# openTPM.net
KiCad netlist of a schematic drawn in EAGLE
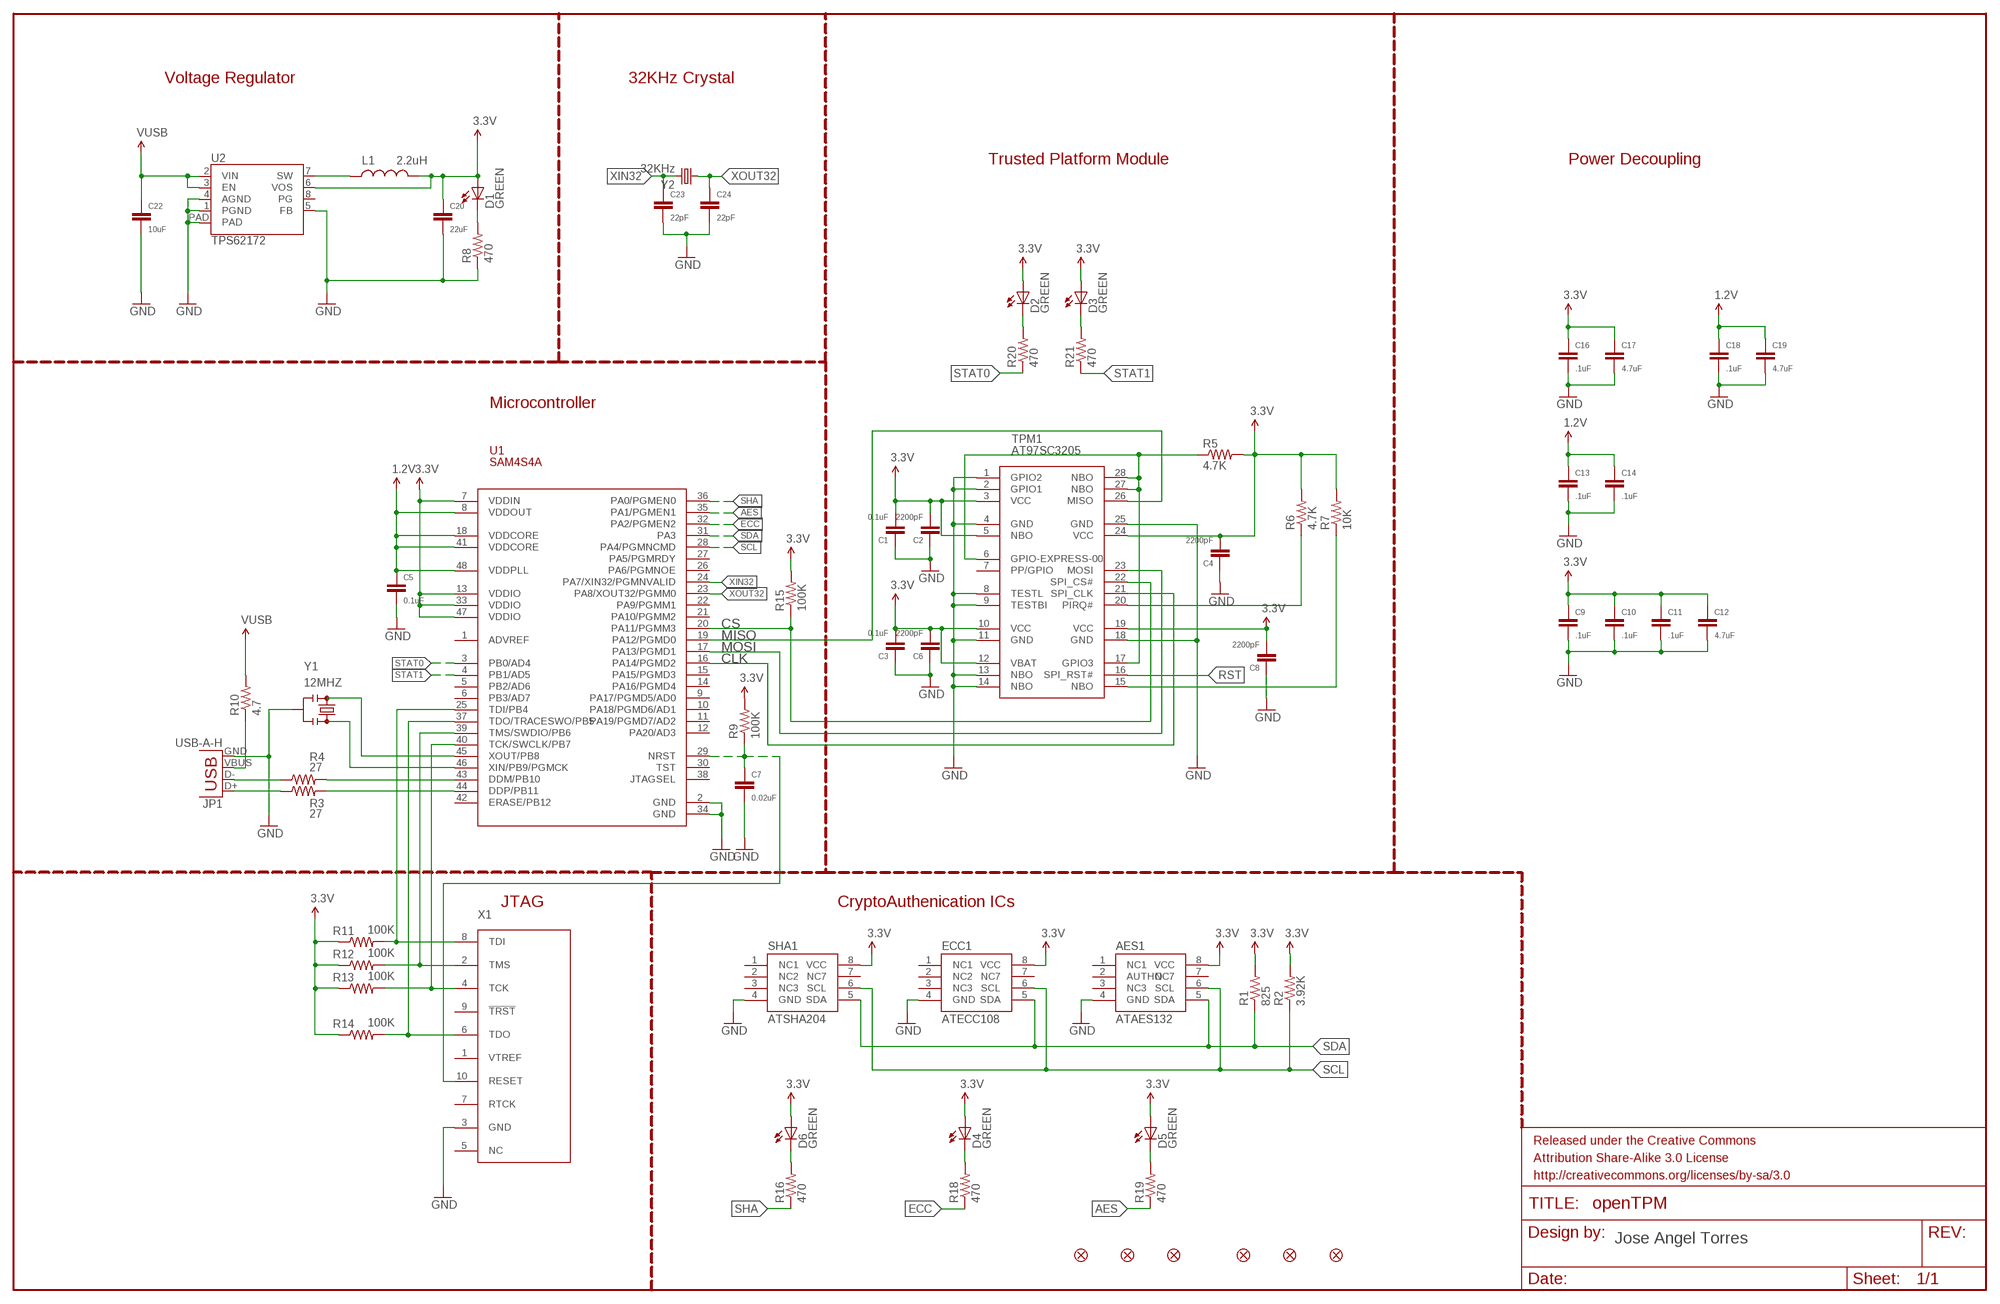
[diagram p0: schematic, sheet 1]

(export (version "E")
  (design (tool "Eeschema 10.0.6"))
  (components
    (comp (ref "AES1")
      (value "ATAES132")
      (footprint "eagle-import:CRYPTOTRONIX_SOIC8")
      (libsource (lib "eagle-import") (part "CRYPTOTRONIX_ATAES132"))
    )
    (comp (ref "C1")
      (value "0.1uF")
      (footprint "eagle-import:0201")
      (libsource (lib "eagle-import") (part "CAPACITOR.0201"))
    )
    (comp (ref "C2")
      (value "2200pF")
      (footprint "eagle-import:0201")
      (libsource (lib "eagle-import") (part "CAPACITOR.0201"))
    )
    (comp (ref "C3")
      (value "0.1uF")
      (footprint "eagle-import:0201")
      (libsource (lib "eagle-import") (part "CAPACITOR.0201"))
    )
    (comp (ref "C4")
      (value "2200pF")
      (footprint "eagle-import:0201")
      (libsource (lib "eagle-import") (part "CAPACITOR.0201"))
    )
    (comp (ref "C5")
      (value "0.1uF")
      (footprint "eagle-import:0201")
      (libsource (lib "eagle-import") (part "CAPACITOR.0201"))
    )
    (comp (ref "C6")
      (value "2200pF")
      (footprint "eagle-import:0201")
      (libsource (lib "eagle-import") (part "CAPACITOR.0201"))
    )
    (comp (ref "C7")
      (value "0.02uF")
      (footprint "eagle-import:0201")
      (libsource (lib "eagle-import") (part "CAPACITOR.0201"))
    )
    (comp (ref "C8")
      (value "2200pF")
      (footprint "eagle-import:0201")
      (libsource (lib "eagle-import") (part "CAPACITOR.0201"))
    )
    (comp (ref "C9")
      (value ".1uF")
      (footprint "eagle-import:0201")
      (libsource (lib "eagle-import") (part "CAPACITOR.0201"))
    )
    (comp (ref "C10")
      (value ".1uF")
      (footprint "eagle-import:0201")
      (libsource (lib "eagle-import") (part "CAPACITOR.0201"))
    )
    (comp (ref "C11")
      (value ".1uF")
      (footprint "eagle-import:0201")
      (libsource (lib "eagle-import") (part "CAPACITOR.0201"))
    )
    (comp (ref "C12")
      (value "4.7uF")
      (footprint "eagle-import:0402")
      (libsource (lib "eagle-import") (part "CAPACITOR.0402"))
    )
    (comp (ref "C13")
      (value ".1uF")
      (footprint "eagle-import:0201")
      (libsource (lib "eagle-import") (part "CAPACITOR.0201"))
    )
    (comp (ref "C14")
      (value ".1uF")
      (footprint "eagle-import:0201")
      (libsource (lib "eagle-import") (part "CAPACITOR.0201"))
    )
    (comp (ref "C16")
      (value ".1uF")
      (footprint "eagle-import:0201")
      (libsource (lib "eagle-import") (part "CAPACITOR.0201"))
    )
    (comp (ref "C17")
      (value "4.7uF")
      (footprint "eagle-import:0402")
      (libsource (lib "eagle-import") (part "CAPACITOR.0402"))
    )
    (comp (ref "C18")
      (value ".1uF")
      (footprint "eagle-import:0201")
      (libsource (lib "eagle-import") (part "CAPACITOR.0201"))
    )
    (comp (ref "C19")
      (value "4.7uF")
      (footprint "eagle-import:0402")
      (libsource (lib "eagle-import") (part "CAPACITOR.0402"))
    )
    (comp (ref "C20")
      (value "22uF")
      (footprint "eagle-import:0603")
      (libsource (lib "eagle-import") (part "CAPACITOR.0603"))
    )
    (comp (ref "C22")
      (value "10uF")
      (footprint "eagle-import:0402")
      (libsource (lib "eagle-import") (part "CAPACITOR.0402"))
    )
    (comp (ref "C23")
      (value "22pF")
      (footprint "eagle-import:0201")
      (libsource (lib "eagle-import") (part "CAPACITOR.0201"))
    )
    (comp (ref "C24")
      (value "22pF")
      (footprint "eagle-import:0201")
      (libsource (lib "eagle-import") (part "CAPACITOR.0201"))
    )
    (comp (ref "D1")
      (value "GREEN")
      (footprint "eagle-import:SPARKFUN-LED_LED-0603")
      (libsource (lib "eagle-import") (part "SPARKFUN-LED_LED-GREEN0603"))
    )
    (comp (ref "D2")
      (value "GREEN")
      (footprint "eagle-import:SPARKFUN-LED_LED-0603")
      (libsource (lib "eagle-import") (part "SPARKFUN-LED_LED-GREEN0603"))
    )
    (comp (ref "D3")
      (value "GREEN")
      (footprint "eagle-import:SPARKFUN-LED_LED-0603")
      (libsource (lib "eagle-import") (part "SPARKFUN-LED_LED-GREEN0603"))
    )
    (comp (ref "D4")
      (value "GREEN")
      (footprint "eagle-import:SPARKFUN-LED_LED-0603")
      (libsource (lib "eagle-import") (part "SPARKFUN-LED_LED-GREEN0603"))
    )
    (comp (ref "D5")
      (value "GREEN")
      (footprint "eagle-import:SPARKFUN-LED_LED-0603")
      (libsource (lib "eagle-import") (part "SPARKFUN-LED_LED-GREEN0603"))
    )
    (comp (ref "D6")
      (value "GREEN")
      (footprint "eagle-import:SPARKFUN-LED_LED-0603")
      (libsource (lib "eagle-import") (part "SPARKFUN-LED_LED-GREEN0603"))
    )
    (comp (ref "ECC1")
      (value "ATECC108")
      (footprint "eagle-import:CRYPTOTRONIX_SOIC8")
      (libsource (lib "eagle-import") (part "CRYPTOTRONIX_ATECC108"))
    )
    (comp (ref "FID1")
      (value "SPARKFUN-AESTHETICS_FIDUCIAL1X2.5")
      (footprint "eagle-import:SPARKFUN-AESTHETICS_FIDUCIAL-1X2.5")
      (libsource (lib "eagle-import") (part "SPARKFUN-AESTHETICS_FIDUCIAL1X2.5"))
    )
    (comp (ref "FID2")
      (value "SPARKFUN-AESTHETICS_FIDUCIAL1X2.5")
      (footprint "eagle-import:SPARKFUN-AESTHETICS_FIDUCIAL-1X2.5")
      (libsource (lib "eagle-import") (part "SPARKFUN-AESTHETICS_FIDUCIAL1X2.5"))
    )
    (comp (ref "FID3")
      (value "SPARKFUN-AESTHETICS_FIDUCIAL1X2.5")
      (footprint "eagle-import:SPARKFUN-AESTHETICS_FIDUCIAL-1X2.5")
      (libsource (lib "eagle-import") (part "SPARKFUN-AESTHETICS_FIDUCIAL1X2.5"))
    )
    (comp (ref "FID4")
      (value "SPARKFUN-AESTHETICS_FIDUCIAL1X2.5")
      (footprint "eagle-import:SPARKFUN-AESTHETICS_FIDUCIAL-1X2.5")
      (libsource (lib "eagle-import") (part "SPARKFUN-AESTHETICS_FIDUCIAL1X2.5"))
    )
    (comp (ref "FID5")
      (value "SPARKFUN-AESTHETICS_FIDUCIAL1X2.5")
      (footprint "eagle-import:SPARKFUN-AESTHETICS_FIDUCIAL-1X2.5")
      (libsource (lib "eagle-import") (part "SPARKFUN-AESTHETICS_FIDUCIAL1X2.5"))
    )
    (comp (ref "FID6")
      (value "SPARKFUN-AESTHETICS_FIDUCIAL1X2.5")
      (footprint "eagle-import:SPARKFUN-AESTHETICS_FIDUCIAL-1X2.5")
      (libsource (lib "eagle-import") (part "SPARKFUN-AESTHETICS_FIDUCIAL1X2.5"))
    )
    (comp (ref "JP1")
      (value "USB-A-H")
      (footprint "eagle-import:USB-A-H")
      (libsource (lib "eagle-import") (part "USB-A-H"))
    )
    (comp (ref "L1")
      (value "2.2uH")
      (footprint "eagle-import:C0402")
      (libsource (lib "eagle-import") (part "INDUCTOR0402"))
    )
    (comp (ref "R1")
      (value "825")
      (footprint "eagle-import:0201")
      (libsource (lib "eagle-import") (part "RESISTOR.0201"))
    )
    (comp (ref "R2")
      (value "3.92K")
      (footprint "eagle-import:0201")
      (libsource (lib "eagle-import") (part "RESISTOR.0201"))
    )
    (comp (ref "R3")
      (value "27")
      (footprint "eagle-import:0402")
      (libsource (lib "eagle-import") (part "RESISTOR.0402"))
    )
    (comp (ref "R4")
      (value "27")
      (footprint "eagle-import:0402")
      (libsource (lib "eagle-import") (part "RESISTOR.0402"))
    )
    (comp (ref "R5")
      (value "4.7K")
      (footprint "eagle-import:0201")
      (libsource (lib "eagle-import") (part "RESISTOR.0201"))
    )
    (comp (ref "R6")
      (value "4.7K")
      (footprint "eagle-import:0201")
      (libsource (lib "eagle-import") (part "RESISTOR.0201"))
    )
    (comp (ref "R7")
      (value "10K")
      (footprint "eagle-import:0201")
      (libsource (lib "eagle-import") (part "RESISTOR.0201"))
    )
    (comp (ref "R8")
      (value "470")
      (footprint "eagle-import:0402")
      (libsource (lib "eagle-import") (part "RESISTOR.0402"))
    )
    (comp (ref "R9")
      (value "100K")
      (footprint "eagle-import:0201")
      (libsource (lib "eagle-import") (part "RESISTOR.0201"))
    )
    (comp (ref "R10")
      (value "4.7")
      (footprint "eagle-import:0402")
      (libsource (lib "eagle-import") (part "RESISTOR.0402"))
    )
    (comp (ref "R11")
      (value "100K")
      (footprint "eagle-import:0201")
      (libsource (lib "eagle-import") (part "RESISTOR.0201"))
    )
    (comp (ref "R12")
      (value "100K")
      (footprint "eagle-import:0201")
      (libsource (lib "eagle-import") (part "RESISTOR.0201"))
    )
    (comp (ref "R13")
      (value "100K")
      (footprint "eagle-import:0201")
      (libsource (lib "eagle-import") (part "RESISTOR.0201"))
    )
    (comp (ref "R14")
      (value "100K")
      (footprint "eagle-import:0201")
      (libsource (lib "eagle-import") (part "RESISTOR.0201"))
    )
    (comp (ref "R15")
      (value "100K")
      (footprint "eagle-import:0201")
      (libsource (lib "eagle-import") (part "RESISTOR.0201"))
    )
    (comp (ref "R16")
      (value "470")
      (footprint "eagle-import:0201")
      (libsource (lib "eagle-import") (part "RESISTOR.0201"))
    )
    (comp (ref "R18")
      (value "470")
      (footprint "eagle-import:0201")
      (libsource (lib "eagle-import") (part "RESISTOR.0201"))
    )
    (comp (ref "R19")
      (value "470")
      (footprint "eagle-import:0201")
      (libsource (lib "eagle-import") (part "RESISTOR.0201"))
    )
    (comp (ref "R20")
      (value "470")
      (footprint "eagle-import:0201")
      (libsource (lib "eagle-import") (part "RESISTOR.0201"))
    )
    (comp (ref "R21")
      (value "470")
      (footprint "eagle-import:0201")
      (libsource (lib "eagle-import") (part "RESISTOR.0201"))
    )
    (comp (ref "SHA1")
      (value "ATSHA204")
      (footprint "eagle-import:CRYPTOTRONIX_SOIC8")
      (libsource (lib "eagle-import") (part "CRYPTOTRONIX_ATSHA204"))
    )
    (comp (ref "TPM1")
      (value "AT97SC3205")
      (footprint "eagle-import:TSSOP28")
      (libsource (lib "eagle-import") (part "AT97SC3205"))
    )
    (comp (ref "U1")
      (value "SAM4S4A")
      (footprint "eagle-import:LQFP-48")
      (libsource (lib "eagle-import") (part "SAM4S4A"))
    )
    (comp (ref "U2")
      (value "TPS62172")
      (footprint "eagle-import:WSON-8-PAD")
      (libsource (lib "eagle-import") (part "TPS62172"))
    )
    (comp (ref "X1")
      (value "TC2050-NL-MCP-NL")
      (footprint "eagle-import:TC2030-MCP-NL")
      (libsource (lib "eagle-import") (part "TC2050-NL-MCP-NL"))
    )
    (comp (ref "Y1")
      (value "12MHZ")
      (footprint "eagle-import:RESONATOR-SMD")
      (libsource (lib "eagle-import") (part "RESONATOR12MHZ"))
    )
    (comp (ref "Y2")
      (value "32KHz")
      (footprint "eagle-import:CRYSTAL-32KHZ-SMD_EPSON_MC146")
      (libsource (lib "eagle-import") (part "CRYSTALEPSONMC146"))
    )
  )
  (nets
    (net (code "1") (name "/CLK") (class "Default")
      (node (ref "TPM1") (pin "21") (pinfunction "SPI_CLK_21") (pintype "bidirectional"))
      (node (ref "U1") (pin "16") (pinfunction "PA14/PGMD2_16") (pintype "bidirectional"))
    )
    (net (code "2") (name "/CS") (class "Default")
      (node (ref "R15") (pin "1") (pinfunction "1_1") (pintype "passive"))
      (node (ref "TPM1") (pin "22") (pinfunction "SPI_CS#_22") (pintype "power_in"))
      (node (ref "U1") (pin "20") (pinfunction "PA11/PGMM3_20") (pintype "bidirectional"))
    )
    (net (code "3") (name "/MISO") (class "Default")
      (node (ref "TPM1") (pin "26") (pinfunction "MISO_26") (pintype "power_in"))
      (node (ref "U1") (pin "19") (pinfunction "PA12/PGMD0_19") (pintype "bidirectional"))
    )
    (net (code "4") (name "/MOSI") (class "Default")
      (node (ref "TPM1") (pin "23") (pinfunction "MOSI_23") (pintype "power_in"))
      (node (ref "U1") (pin "17") (pinfunction "PA13/PGMD1_17") (pintype "bidirectional"))
    )
    (net (code "5") (name "1.2V") (class "Default")
      (node (ref "C13") (pin "1") (pinfunction "1_1") (pintype "passive"))
      (node (ref "C14") (pin "1") (pinfunction "1_1") (pintype "passive"))
      (node (ref "C18") (pin "1") (pinfunction "1_1") (pintype "passive"))
      (node (ref "C19") (pin "1") (pinfunction "1_1") (pintype "passive"))
      (node (ref "C5") (pin "1") (pinfunction "1_1") (pintype "passive"))
      (node (ref "U1") (pin "18") (pinfunction "VDDCORE_18") (pintype "bidirectional"))
      (node (ref "U1") (pin "41") (pinfunction "VDDCORE_41") (pintype "bidirectional"))
      (node (ref "U1") (pin "48") (pinfunction "VDDPLL_48") (pintype "bidirectional"))
      (node (ref "U1") (pin "8") (pinfunction "VDDOUT_8") (pintype "bidirectional"))
    )
    (net (code "6") (name "3.3V") (class "Default")
      (node (ref "AES1") (pin "8") (pinfunction "VCC_8") (pintype "power_in"))
      (node (ref "C1") (pin "2") (pinfunction "2_2") (pintype "passive"))
      (node (ref "C10") (pin "1") (pinfunction "1_1") (pintype "passive"))
      (node (ref "C11") (pin "1") (pinfunction "1_1") (pintype "passive"))
      (node (ref "C12") (pin "1") (pinfunction "1_1") (pintype "passive"))
      (node (ref "C16") (pin "1") (pinfunction "1_1") (pintype "passive"))
      (node (ref "C17") (pin "1") (pinfunction "1_1") (pintype "passive"))
      (node (ref "C2") (pin "2") (pinfunction "2_2") (pintype "passive"))
      (node (ref "C20") (pin "1") (pinfunction "1_1") (pintype "passive"))
      (node (ref "C3") (pin "2") (pinfunction "2_2") (pintype "passive"))
      (node (ref "C4") (pin "2") (pinfunction "2_2") (pintype "passive"))
      (node (ref "C6") (pin "2") (pinfunction "2_2") (pintype "passive"))
      (node (ref "C8") (pin "2") (pinfunction "2_2") (pintype "passive"))
      (node (ref "C9") (pin "1") (pinfunction "1_1") (pintype "passive"))
      (node (ref "D1") (pin "A") (pinfunction "A_A") (pintype "passive"))
      (node (ref "D2") (pin "A") (pinfunction "A_A") (pintype "passive"))
      (node (ref "D3") (pin "A") (pinfunction "A_A") (pintype "passive"))
      (node (ref "D4") (pin "A") (pinfunction "A_A") (pintype "passive"))
      (node (ref "D5") (pin "A") (pinfunction "A_A") (pintype "passive"))
      (node (ref "D6") (pin "A") (pinfunction "A_A") (pintype "passive"))
      (node (ref "ECC1") (pin "8") (pinfunction "VCC_8") (pintype "power_in"))
      (node (ref "L1") (pin "2") (pinfunction "2_2") (pintype "passive"))
      (node (ref "R1") (pin "2") (pinfunction "2_2") (pintype "passive"))
      (node (ref "R11") (pin "1") (pinfunction "1_1") (pintype "passive"))
      (node (ref "R12") (pin "1") (pinfunction "1_1") (pintype "passive"))
      (node (ref "R13") (pin "1") (pinfunction "1_1") (pintype "passive"))
      (node (ref "R14") (pin "1") (pinfunction "1_1") (pintype "passive"))
      (node (ref "R15") (pin "2") (pinfunction "2_2") (pintype "passive"))
      (node (ref "R2") (pin "2") (pinfunction "2_2") (pintype "passive"))
      (node (ref "R5") (pin "2") (pinfunction "2_2") (pintype "passive"))
      (node (ref "R6") (pin "2") (pinfunction "2_2") (pintype "passive"))
      (node (ref "R7") (pin "2") (pinfunction "2_2") (pintype "passive"))
      (node (ref "R9") (pin "2") (pinfunction "2_2") (pintype "passive"))
      (node (ref "SHA1") (pin "8") (pinfunction "VCC_8") (pintype "power_in"))
      (node (ref "TPM1") (pin "10") (pinfunction "VCC_10") (pintype "power_in"))
      (node (ref "TPM1") (pin "12") (pinfunction "VBAT_12") (pintype "bidirectional"))
      (node (ref "TPM1") (pin "19") (pinfunction "VCC_19") (pintype "power_in"))
      (node (ref "TPM1") (pin "24") (pinfunction "VCC_24") (pintype "power_in"))
      (node (ref "TPM1") (pin "3") (pinfunction "VCC_3") (pintype "power_in"))
      (node (ref "TPM1") (pin "5") (pinfunction "NBO_5") (pintype "bidirectional"))
      (node (ref "U1") (pin "13") (pinfunction "VDDIO_13") (pintype "bidirectional"))
      (node (ref "U1") (pin "33") (pinfunction "VDDIO_33") (pintype "bidirectional"))
      (node (ref "U1") (pin "47") (pinfunction "VDDIO_47") (pintype "bidirectional"))
      (node (ref "U1") (pin "7") (pinfunction "VDDIN_7") (pintype "bidirectional"))
      (node (ref "U2") (pin "6") (pinfunction "VOS_6") (pintype "bidirectional"))
    )
    (net (code "7") (name "AES") (class "Default")
      (node (ref "R19") (pin "1") (pinfunction "1_1") (pintype "passive"))
      (node (ref "U1") (pin "35") (pinfunction "PA1/PGMEN1_35") (pintype "bidirectional"))
    )
    (net (code "8") (name "ECC") (class "Default")
      (node (ref "R18") (pin "1") (pinfunction "1_1") (pintype "passive"))
      (node (ref "U1") (pin "32") (pinfunction "PA2/PGMEN2_32") (pintype "bidirectional"))
    )
    (net (code "9") (name "GND") (class "Default")
      (node (ref "AES1") (pin "4") (pinfunction "GND_4") (pintype "power_in"))
      (node (ref "C1") (pin "1") (pinfunction "1_1") (pintype "passive"))
      (node (ref "C10") (pin "2") (pinfunction "2_2") (pintype "passive"))
      (node (ref "C11") (pin "2") (pinfunction "2_2") (pintype "passive"))
      (node (ref "C12") (pin "2") (pinfunction "2_2") (pintype "passive"))
      (node (ref "C13") (pin "2") (pinfunction "2_2") (pintype "passive"))
      (node (ref "C14") (pin "2") (pinfunction "2_2") (pintype "passive"))
      (node (ref "C16") (pin "2") (pinfunction "2_2") (pintype "passive"))
      (node (ref "C17") (pin "2") (pinfunction "2_2") (pintype "passive"))
      (node (ref "C18") (pin "2") (pinfunction "2_2") (pintype "passive"))
      (node (ref "C19") (pin "2") (pinfunction "2_2") (pintype "passive"))
      (node (ref "C2") (pin "1") (pinfunction "1_1") (pintype "passive"))
      (node (ref "C20") (pin "2") (pinfunction "2_2") (pintype "passive"))
      (node (ref "C22") (pin "2") (pinfunction "2_2") (pintype "passive"))
      (node (ref "C23") (pin "2") (pinfunction "2_2") (pintype "passive"))
      (node (ref "C24") (pin "2") (pinfunction "2_2") (pintype "passive"))
      (node (ref "C3") (pin "1") (pinfunction "1_1") (pintype "passive"))
      (node (ref "C4") (pin "1") (pinfunction "1_1") (pintype "passive"))
      (node (ref "C5") (pin "2") (pinfunction "2_2") (pintype "passive"))
      (node (ref "C6") (pin "1") (pinfunction "1_1") (pintype "passive"))
      (node (ref "C7") (pin "2") (pinfunction "2_2") (pintype "passive"))
      (node (ref "C8") (pin "1") (pinfunction "1_1") (pintype "passive"))
      (node (ref "C9") (pin "2") (pinfunction "2_2") (pintype "passive"))
      (node (ref "ECC1") (pin "4") (pinfunction "GND_4") (pintype "power_in"))
      (node (ref "JP1") (pin "GND") (pinfunction "GND_GND") (pintype "bidirectional"))
      (node (ref "R8") (pin "1") (pinfunction "1_1") (pintype "passive"))
      (node (ref "SHA1") (pin "4") (pinfunction "GND_4") (pintype "power_in"))
      (node (ref "TPM1") (pin "1") (pinfunction "GPIO2_1") (pintype "bidirectional"))
      (node (ref "TPM1") (pin "11") (pinfunction "GND_11") (pintype "power_in"))
      (node (ref "TPM1") (pin "13") (pinfunction "NBO_13") (pintype "bidirectional"))
      (node (ref "TPM1") (pin "14") (pinfunction "NBO_14") (pintype "bidirectional"))
      (node (ref "TPM1") (pin "18") (pinfunction "GND_18") (pintype "power_in"))
      (node (ref "TPM1") (pin "2") (pinfunction "GPIO1_2") (pintype "bidirectional"))
      (node (ref "TPM1") (pin "25") (pinfunction "GND_25") (pintype "power_in"))
      (node (ref "TPM1") (pin "4") (pinfunction "GND_4") (pintype "power_in"))
      (node (ref "TPM1") (pin "8") (pinfunction "TESTL_8") (pintype "bidirectional"))
      (node (ref "TPM1") (pin "9") (pinfunction "TESTBI_9") (pintype "bidirectional"))
      (node (ref "U1") (pin "2") (pinfunction "GND_2") (pintype "bidirectional"))
      (node (ref "U1") (pin "34") (pinfunction "GND_34") (pintype "bidirectional"))
      (node (ref "U2") (pin "1") (pinfunction "PGND_1") (pintype "bidirectional"))
      (node (ref "U2") (pin "4") (pinfunction "AGND_4") (pintype "bidirectional"))
      (node (ref "U2") (pin "5") (pinfunction "FB_5") (pintype "bidirectional"))
      (node (ref "U2") (pin "PAD") (pinfunction "PAD_PAD") (pintype "bidirectional"))
      (node (ref "X1") (pin "3") (pinfunction "GND_3") (pintype "bidirectional"))
      (node (ref "Y1") (pin "2") (pinfunction "2_2") (pintype "passive"))
    )
    (net (code "10") (name "Net-(D1-PadC)") (class "Default")
      (node (ref "D1") (pin "C") (pinfunction "C_C") (pintype "passive"))
      (node (ref "R8") (pin "2") (pinfunction "2_2") (pintype "passive"))
    )
    (net (code "11") (name "Net-(D2-PadC)") (class "Default")
      (node (ref "D2") (pin "C") (pinfunction "C_C") (pintype "passive"))
      (node (ref "R20") (pin "2") (pinfunction "2_2") (pintype "passive"))
    )
    (net (code "12") (name "Net-(D3-PadC)") (class "Default")
      (node (ref "D3") (pin "C") (pinfunction "C_C") (pintype "passive"))
      (node (ref "R21") (pin "2") (pinfunction "2_2") (pintype "passive"))
    )
    (net (code "13") (name "Net-(D4-PadC)") (class "Default")
      (node (ref "D4") (pin "C") (pinfunction "C_C") (pintype "passive"))
      (node (ref "R18") (pin "2") (pinfunction "2_2") (pintype "passive"))
    )
    (net (code "14") (name "Net-(D5-PadC)") (class "Default")
      (node (ref "D5") (pin "C") (pinfunction "C_C") (pintype "passive"))
      (node (ref "R19") (pin "2") (pinfunction "2_2") (pintype "passive"))
    )
    (net (code "15") (name "Net-(D6-PadC)") (class "Default")
      (node (ref "D6") (pin "C") (pinfunction "C_C") (pintype "passive"))
      (node (ref "R16") (pin "2") (pinfunction "2_2") (pintype "passive"))
    )
    (net (code "16") (name "Net-(JP1-PadD+)") (class "Default")
      (node (ref "JP1") (pin "D+") (pinfunction "D+_D+") (pintype "bidirectional"))
      (node (ref "R3") (pin "1") (pinfunction "1_1") (pintype "passive"))
    )
    (net (code "17") (name "Net-(JP1-PadD-)") (class "Default")
      (node (ref "JP1") (pin "D-") (pinfunction "D-_D-") (pintype "bidirectional"))
      (node (ref "R4") (pin "1") (pinfunction "1_1") (pintype "passive"))
    )
    (net (code "18") (name "Net-(JP1-PadVBUS)") (class "Default")
      (node (ref "JP1") (pin "VBUS") (pinfunction "VBUS_VBUS") (pintype "bidirectional"))
      (node (ref "R10") (pin "1") (pinfunction "1_1") (pintype "passive"))
    )
    (net (code "19") (name "Net-(R7-Pad1)") (class "Default")
      (node (ref "R7") (pin "1") (pinfunction "1_1") (pintype "passive"))
      (node (ref "TPM1") (pin "15") (pinfunction "NBO_15") (pintype "bidirectional"))
    )
    (net (code "20") (name "Net-(TPM1-GPIO-EXPRESS-00)") (class "Default")
      (node (ref "R5") (pin "1") (pinfunction "1_1") (pintype "passive"))
      (node (ref "TPM1") (pin "17") (pinfunction "GPIO3_17") (pintype "power_in"))
      (node (ref "TPM1") (pin "27") (pinfunction "NBO_27") (pintype "bidirectional"))
      (node (ref "TPM1") (pin "28") (pinfunction "NBO_28") (pintype "bidirectional"))
      (node (ref "TPM1") (pin "6") (pinfunction "GPIO-EXPRESS-00_6") (pintype "power_in"))
    )
    (net (code "21") (name "Net-(TPM1-PIRQ#)") (class "Default")
      (node (ref "R6") (pin "1") (pinfunction "1_1") (pintype "passive"))
      (node (ref "TPM1") (pin "20") (pinfunction "PIRQ#_20") (pintype "power_in"))
    )
    (net (code "22") (name "Net-(U1-DDM{slash}PB10)") (class "Default")
      (node (ref "R4") (pin "2") (pinfunction "2_2") (pintype "passive"))
      (node (ref "U1") (pin "43") (pinfunction "DDM/PB10_43") (pintype "bidirectional"))
    )
    (net (code "23") (name "Net-(U1-DDP{slash}PB11)") (class "Default")
      (node (ref "R3") (pin "2") (pinfunction "2_2") (pintype "passive"))
      (node (ref "U1") (pin "44") (pinfunction "DDP/PB11_44") (pintype "bidirectional"))
    )
    (net (code "24") (name "Net-(U1-TCK{slash}SWCLK{slash}PB7)") (class "Default")
      (node (ref "R13") (pin "2") (pinfunction "2_2") (pintype "passive"))
      (node (ref "U1") (pin "40") (pinfunction "TCK/SWCLK/PB7_40") (pintype "bidirectional"))
      (node (ref "X1") (pin "4") (pinfunction "TCK_4") (pintype "bidirectional"))
    )
    (net (code "25") (name "Net-(U1-TDI{slash}PB4)") (class "Default")
      (node (ref "R11") (pin "2") (pinfunction "2_2") (pintype "passive"))
      (node (ref "U1") (pin "25") (pinfunction "TDI/PB4_25") (pintype "bidirectional"))
      (node (ref "X1") (pin "8") (pinfunction "TDI_8") (pintype "bidirectional"))
    )
    (net (code "26") (name "Net-(U1-TDO{slash}TRACESWO{slash}PB5)") (class "Default")
      (node (ref "R14") (pin "2") (pinfunction "2_2") (pintype "passive"))
      (node (ref "U1") (pin "37") (pinfunction "TDO/TRACESWO/PB5_37") (pintype "bidirectional"))
      (node (ref "X1") (pin "6") (pinfunction "TDO_6") (pintype "bidirectional"))
    )
    (net (code "27") (name "Net-(U1-TMS{slash}SWDIO{slash}PB6)") (class "Default")
      (node (ref "R12") (pin "2") (pinfunction "2_2") (pintype "passive"))
      (node (ref "U1") (pin "39") (pinfunction "TMS/SWDIO/PB6_39") (pintype "bidirectional"))
      (node (ref "X1") (pin "2") (pinfunction "TMS_2") (pintype "bidirectional"))
    )
    (net (code "28") (name "Net-(U1-XIN{slash}PB9{slash}PGMCK)") (class "Default")
      (node (ref "U1") (pin "46") (pinfunction "XIN/PB9/PGMCK_46") (pintype "bidirectional"))
      (node (ref "Y1") (pin "3") (pinfunction "3_3") (pintype "passive"))
    )
    (net (code "29") (name "Net-(U1-XOUT{slash}PB8)") (class "Default")
      (node (ref "U1") (pin "45") (pinfunction "XOUT/PB8_45") (pintype "bidirectional"))
      (node (ref "Y1") (pin "1") (pinfunction "1_1") (pintype "passive"))
    )
    (net (code "30") (name "Net-(U2-SW)") (class "Default")
      (node (ref "L1") (pin "1") (pinfunction "1_1") (pintype "passive"))
      (node (ref "U2") (pin "7") (pinfunction "SW_7") (pintype "bidirectional"))
    )
    (net (code "31") (name "RST") (class "Default")
      (node (ref "C7") (pin "1") (pinfunction "1_1") (pintype "passive"))
      (node (ref "R9") (pin "1") (pinfunction "1_1") (pintype "passive"))
      (node (ref "TPM1") (pin "16") (pinfunction "SPI_RST#_16") (pintype "bidirectional"))
      (node (ref "U1") (pin "29") (pinfunction "NRST_29") (pintype "bidirectional"))
      (node (ref "X1") (pin "10") (pinfunction "RESET_10") (pintype "bidirectional"))
    )
    (net (code "32") (name "SCL") (class "Default")
      (node (ref "AES1") (pin "6") (pinfunction "SCL_6") (pintype "bidirectional"))
      (node (ref "ECC1") (pin "6") (pinfunction "SCL_6") (pintype "bidirectional"))
      (node (ref "R2") (pin "1") (pinfunction "1_1") (pintype "passive"))
      (node (ref "SHA1") (pin "6") (pinfunction "SCL_6") (pintype "bidirectional"))
      (node (ref "U1") (pin "28") (pinfunction "PA4/PGMNCMD_28") (pintype "bidirectional"))
    )
    (net (code "33") (name "SDA") (class "Default")
      (node (ref "AES1") (pin "5") (pinfunction "SDA_5") (pintype "bidirectional"))
      (node (ref "ECC1") (pin "5") (pinfunction "SDA_5") (pintype "bidirectional"))
      (node (ref "R1") (pin "1") (pinfunction "1_1") (pintype "passive"))
      (node (ref "SHA1") (pin "5") (pinfunction "SDA_5") (pintype "bidirectional"))
      (node (ref "U1") (pin "31") (pinfunction "PA3_31") (pintype "bidirectional"))
    )
    (net (code "34") (name "SHA") (class "Default")
      (node (ref "R16") (pin "1") (pinfunction "1_1") (pintype "passive"))
      (node (ref "U1") (pin "36") (pinfunction "PA0/PGMEN0_36") (pintype "bidirectional"))
    )
    (net (code "35") (name "STAT0") (class "Default")
      (node (ref "R20") (pin "1") (pinfunction "1_1") (pintype "passive"))
      (node (ref "U1") (pin "3") (pinfunction "PB0/AD4_3") (pintype "bidirectional"))
    )
    (net (code "36") (name "STAT1") (class "Default")
      (node (ref "R21") (pin "1") (pinfunction "1_1") (pintype "passive"))
      (node (ref "U1") (pin "4") (pinfunction "PB1/AD5_4") (pintype "bidirectional"))
    )
    (net (code "37") (name "VUSB") (class "Default")
      (node (ref "C22") (pin "1") (pinfunction "1_1") (pintype "passive"))
      (node (ref "R10") (pin "2") (pinfunction "2_2") (pintype "passive"))
      (node (ref "U2") (pin "2") (pinfunction "VIN_2") (pintype "bidirectional"))
      (node (ref "U2") (pin "3") (pinfunction "EN_3") (pintype "bidirectional"))
    )
    (net (code "38") (name "XIN32") (class "Default")
      (node (ref "C23") (pin "1") (pinfunction "1_1") (pintype "passive"))
      (node (ref "U1") (pin "24") (pinfunction "PA7/XIN32/PGMNVALID_24") (pintype "bidirectional"))
      (node (ref "Y2") (pin "P$1") (pinfunction "2_P$1") (pintype "passive"))
    )
    (net (code "39") (name "XOUT32") (class "Default")
      (node (ref "C24") (pin "1") (pinfunction "1_1") (pintype "passive"))
      (node (ref "U1") (pin "23") (pinfunction "PA8/XOUT32/PGMM0_23") (pintype "bidirectional"))
      (node (ref "Y2") (pin "P$2") (pinfunction "1_P$2") (pintype "passive"))
    )
    (net (code "40") (name "unconnected-(AES1-AUTHO-Pad2)") (class "Default")
      (node (ref "AES1") (pin "2") (pinfunction "AUTHO_2") (pintype "bidirectional"))
    )
    (net (code "41") (name "unconnected-(AES1-NC1-Pad1)") (class "Default")
      (node (ref "AES1") (pin "1") (pinfunction "NC1_1") (pintype "no_connect"))
    )
    (net (code "42") (name "unconnected-(AES1-NC3-Pad3)") (class "Default")
      (node (ref "AES1") (pin "3") (pinfunction "NC3_3") (pintype "no_connect"))
    )
    (net (code "43") (name "unconnected-(AES1-NC7-Pad7)") (class "Default")
      (node (ref "AES1") (pin "7") (pinfunction "NC7_7") (pintype "no_connect"))
    )
    (net (code "44") (name "unconnected-(ECC1-NC1-Pad1)") (class "Default")
      (node (ref "ECC1") (pin "1") (pinfunction "NC1_1") (pintype "bidirectional"))
    )
    (net (code "45") (name "unconnected-(ECC1-NC2-Pad2)") (class "Default")
      (node (ref "ECC1") (pin "2") (pinfunction "NC2_2") (pintype "no_connect"))
    )
    (net (code "46") (name "unconnected-(ECC1-NC3-Pad3)") (class "Default")
      (node (ref "ECC1") (pin "3") (pinfunction "NC3_3") (pintype "no_connect"))
    )
    (net (code "47") (name "unconnected-(ECC1-NC7-Pad7)") (class "Default")
      (node (ref "ECC1") (pin "7") (pinfunction "NC7_7") (pintype "no_connect"))
    )
    (net (code "48") (name "unconnected-(SHA1-NC1-Pad1)") (class "Default")
      (node (ref "SHA1") (pin "1") (pinfunction "NC1_1") (pintype "no_connect"))
    )
    (net (code "49") (name "unconnected-(SHA1-NC2-Pad2)") (class "Default")
      (node (ref "SHA1") (pin "2") (pinfunction "NC2_2") (pintype "no_connect"))
    )
    (net (code "50") (name "unconnected-(SHA1-NC3-Pad3)") (class "Default")
      (node (ref "SHA1") (pin "3") (pinfunction "NC3_3") (pintype "no_connect"))
    )
    (net (code "51") (name "unconnected-(SHA1-NC7-Pad7)") (class "Default")
      (node (ref "SHA1") (pin "7") (pinfunction "NC7_7") (pintype "no_connect"))
    )
    (net (code "52") (name "unconnected-(TPM1-PP{slash}GPIO-Pad7)") (class "Default")
      (node (ref "TPM1") (pin "7") (pinfunction "PP/GPIO_7") (pintype "bidirectional"))
    )
    (net (code "53") (name "unconnected-(U1-ADVREF-Pad1)") (class "Default")
      (node (ref "U1") (pin "1") (pinfunction "ADVREF_1") (pintype "bidirectional"))
    )
    (net (code "54") (name "unconnected-(U1-ERASE{slash}PB12-Pad42)") (class "Default")
      (node (ref "U1") (pin "42") (pinfunction "ERASE/PB12_42") (pintype "bidirectional"))
    )
    (net (code "55") (name "unconnected-(U1-JTAGSEL-Pad38)") (class "Default")
      (node (ref "U1") (pin "38") (pinfunction "JTAGSEL_38") (pintype "bidirectional"))
    )
    (net (code "56") (name "unconnected-(U1-PA5{slash}PGMRDY-Pad27)") (class "Default")
      (node (ref "U1") (pin "27") (pinfunction "PA5/PGMRDY_27") (pintype "bidirectional"))
    )
    (net (code "57") (name "unconnected-(U1-PA6{slash}PGMNOE-Pad26)") (class "Default")
      (node (ref "U1") (pin "26") (pinfunction "PA6/PGMNOE_26") (pintype "bidirectional"))
    )
    (net (code "58") (name "unconnected-(U1-PA9{slash}PGMM1-Pad22)") (class "Default")
      (node (ref "U1") (pin "22") (pinfunction "PA9/PGMM1_22") (pintype "bidirectional"))
    )
    (net (code "59") (name "unconnected-(U1-PA10{slash}PGMM2-Pad21)") (class "Default")
      (node (ref "U1") (pin "21") (pinfunction "PA10/PGMM2_21") (pintype "bidirectional"))
    )
    (net (code "60") (name "unconnected-(U1-PA15{slash}PGMD3-Pad15)") (class "Default")
      (node (ref "U1") (pin "15") (pinfunction "PA15/PGMD3_15") (pintype "bidirectional"))
    )
    (net (code "61") (name "unconnected-(U1-PA16{slash}PGMD4-Pad14)") (class "Default")
      (node (ref "U1") (pin "14") (pinfunction "PA16/PGMD4_14") (pintype "bidirectional"))
    )
    (net (code "62") (name "unconnected-(U1-PA17{slash}PGMD5{slash}AD0-Pad9)") (class "Default")
      (node (ref "U1") (pin "9") (pinfunction "PA17/PGMD5/AD0_9") (pintype "bidirectional"))
    )
    (net (code "63") (name "unconnected-(U1-PA18{slash}PGMD6{slash}AD1-Pad10)") (class "Default")
      (node (ref "U1") (pin "10") (pinfunction "PA18/PGMD6/AD1_10") (pintype "bidirectional"))
    )
    (net (code "64") (name "unconnected-(U1-PA19{slash}PGMD7{slash}AD2-Pad11)") (class "Default")
      (node (ref "U1") (pin "11") (pinfunction "PA19/PGMD7/AD2_11") (pintype "bidirectional"))
    )
    (net (code "65") (name "unconnected-(U1-PA20{slash}AD3-Pad12)") (class "Default")
      (node (ref "U1") (pin "12") (pinfunction "PA20/AD3_12") (pintype "bidirectional"))
    )
    (net (code "66") (name "unconnected-(U1-PB2{slash}AD6-Pad5)") (class "Default")
      (node (ref "U1") (pin "5") (pinfunction "PB2/AD6_5") (pintype "bidirectional"))
    )
    (net (code "67") (name "unconnected-(U1-PB3{slash}AD7-Pad6)") (class "Default")
      (node (ref "U1") (pin "6") (pinfunction "PB3/AD7_6") (pintype "bidirectional"))
    )
    (net (code "68") (name "unconnected-(U1-TST-Pad30)") (class "Default")
      (node (ref "U1") (pin "30") (pinfunction "TST_30") (pintype "bidirectional"))
    )
    (net (code "69") (name "unconnected-(U2-PG-Pad8)") (class "Default")
      (node (ref "U2") (pin "8") (pinfunction "PG_8") (pintype "bidirectional"))
    )
    (net (code "70") (name "unconnected-(X1-NC-Pad5)") (class "Default")
      (node (ref "X1") (pin "5") (pinfunction "NC_5") (pintype "bidirectional"))
    )
    (net (code "71") (name "unconnected-(X1-RTCK-Pad7)") (class "Default")
      (node (ref "X1") (pin "7") (pinfunction "RTCK_7") (pintype "bidirectional"))
    )
    (net (code "72") (name "unconnected-(X1-VTREF-Pad1)") (class "Default")
      (node (ref "X1") (pin "1") (pinfunction "VTREF_1") (pintype "bidirectional"))
    )
    (net (code "73") (name "unconnected-(X1-~{TRST}-Pad9)") (class "Default")
      (node (ref "X1") (pin "9") (pinfunction "~{TRST}_9") (pintype "bidirectional"))
    )
  )
)
